# mos.net
KiCad netlist of a schematic drawn in Altium Designer
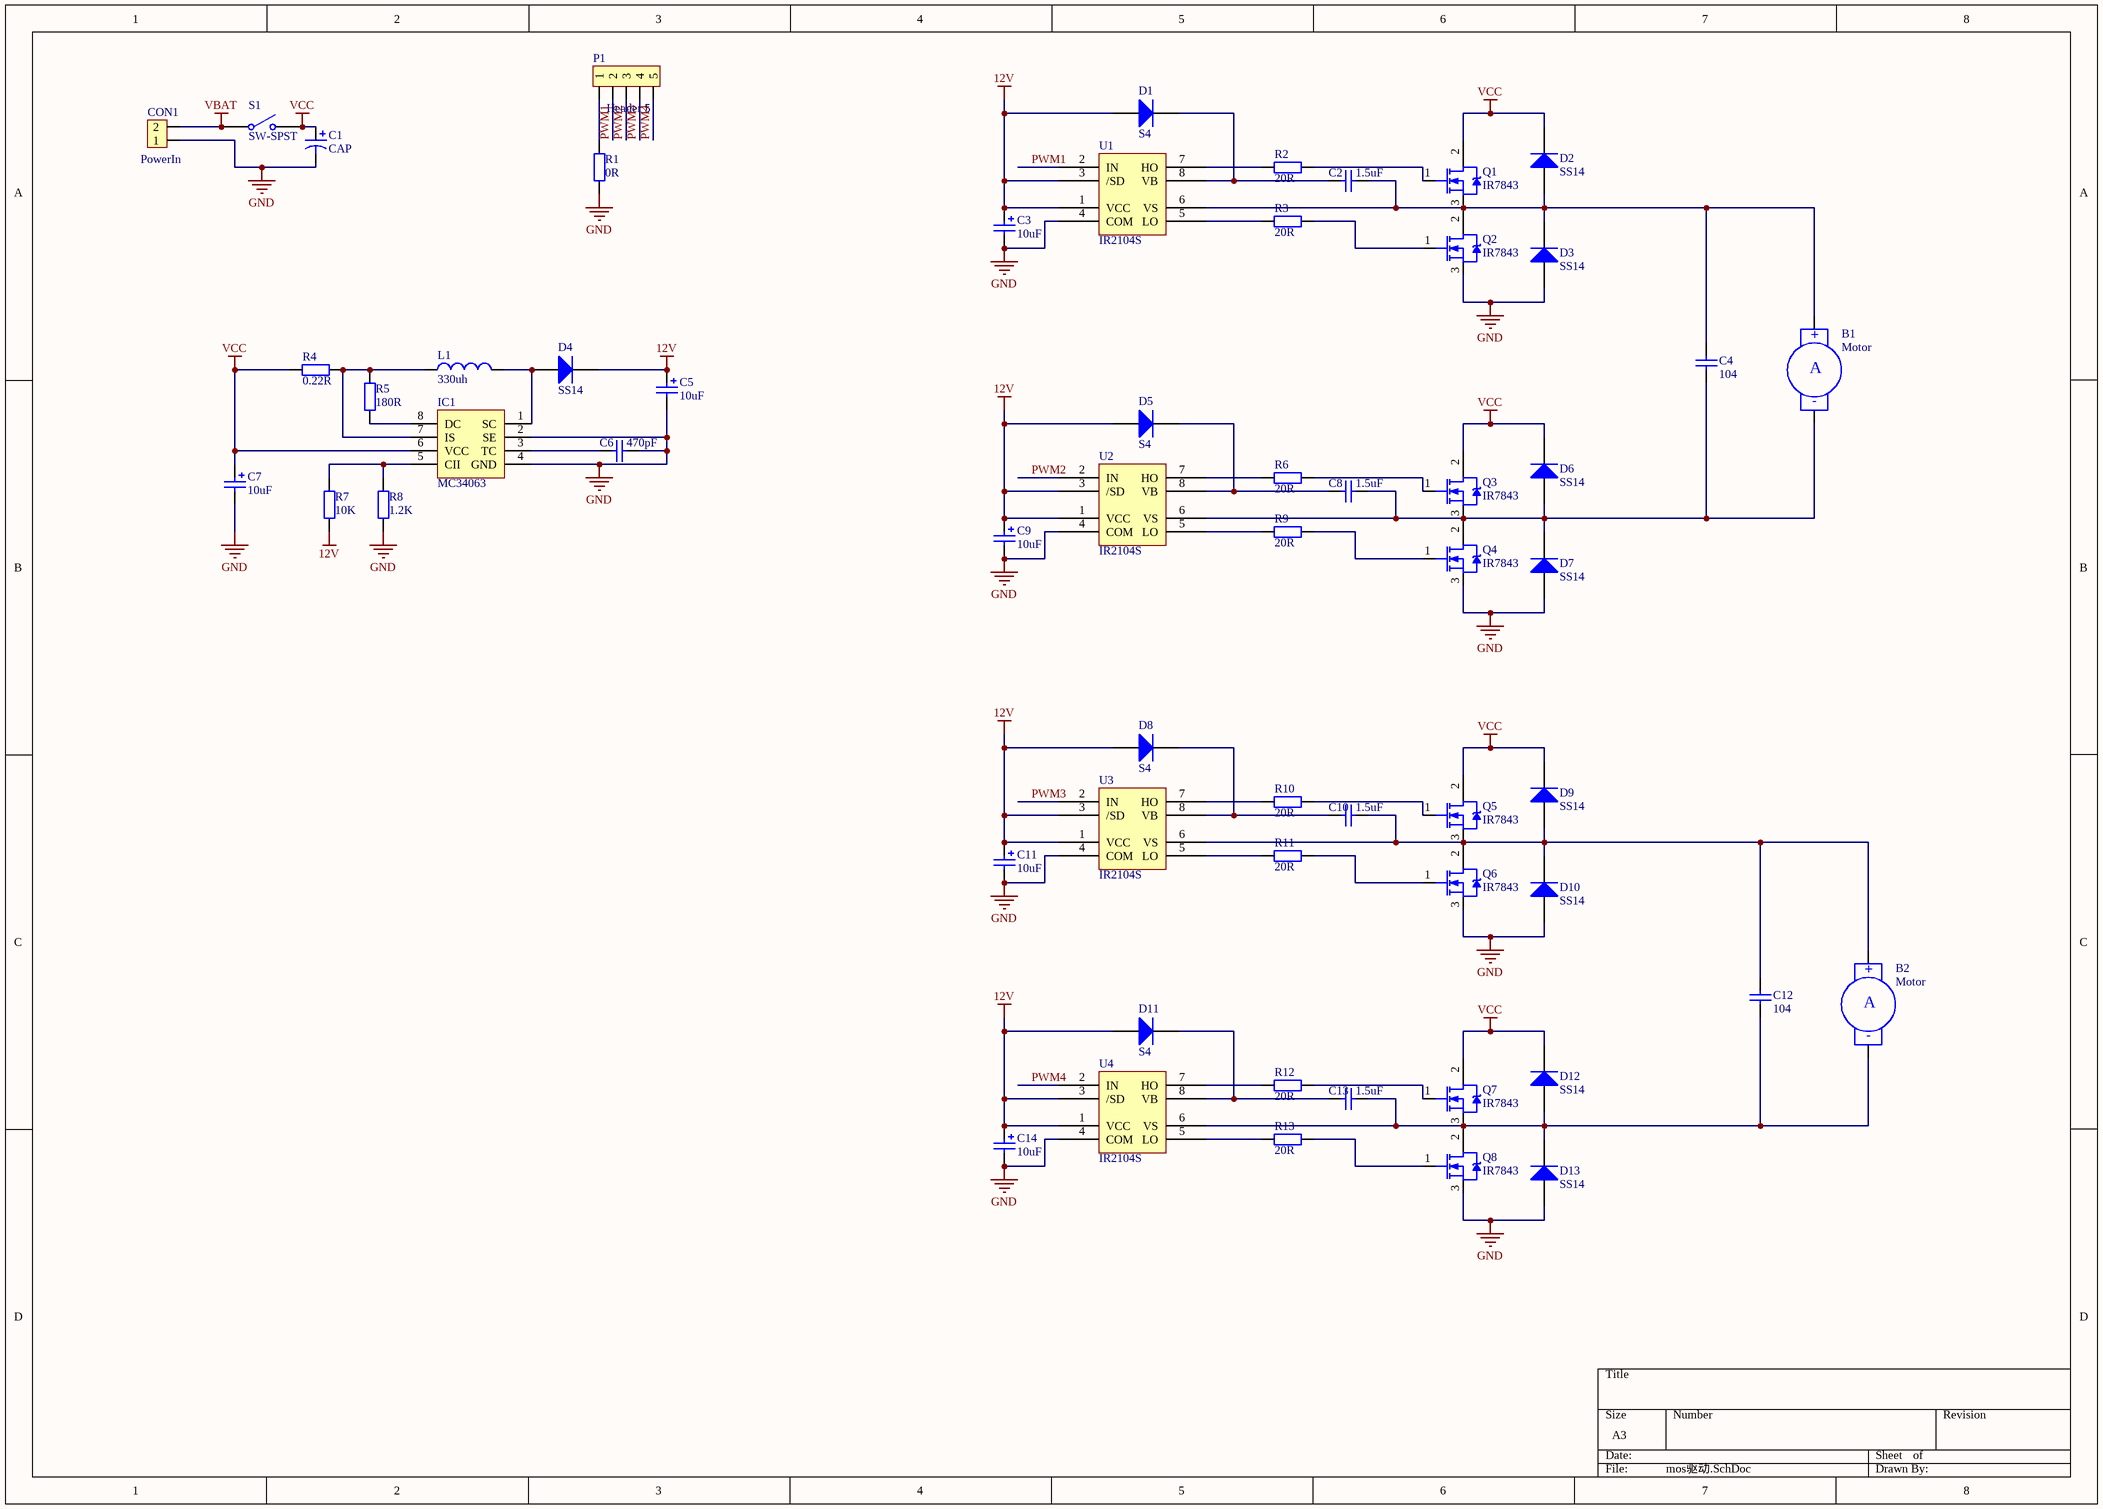
[diagram p0: mos驱动.SchDoc]

(export (version "E")
  (design (tool "Eeschema 10.0.6"))
  (components
    (comp (ref "B1")
      (value "Motor")
      (footprint "KF301-2P")
      (description "Servo Motor")
      (libsource (lib "landzo_mos") (part "Motor Servo"))
    )
    (comp (ref "B2")
      (value "Motor")
      (footprint "KF301-2P")
      (description "Servo Motor")
      (libsource (lib "landzo_mos") (part "Motor Servo"))
    )
    (comp (ref "C1") (value "CAP") (footprint "SMD-EC-F12.5") (libsource (lib "电赛") (part "CAP+")))
    (comp (ref "C2")
      (value "1.5uF")
      (footprint "C2012")
      (description "Capacitor")
      (fields (field (name "Comment") "Cap") (field (name "PUBLISHER") "Altium Limited"))
      (libsource (lib "Miscellaneous Devices") (part "Cap"))
    )
    (comp (ref "C3")
      (value "10uF")
      (footprint "C2012")
      (description "Polarized Capacitor (Radial)")
      (fields (field (name "Comment") "Cap Pol1") (field (name "PUBLISHER") "Altium Limited"))
      (libsource (lib "landzo_mos") (part "Cap Pol1"))
    )
    (comp (ref "C4")
      (value "104")
      (footprint "C2012")
      (description "Capacitor")
      (fields (field (name "Comment") "Cap") (field (name "PUBLISHER") "Altium Limited"))
      (libsource (lib "Miscellaneous Devices") (part "Cap"))
    )
    (comp (ref "C5")
      (value "10uF")
      (footprint "1206C")
      (description "Polarized Capacitor (Radial)")
      (fields (field (name "Comment") "Cap Pol1") (field (name "PUBLISHER") "Altium Limited"))
      (libsource (lib "landzo_mos") (part "Cap Pol1"))
    )
    (comp (ref "C6")
      (value "470pF")
      (footprint "C2012")
      (description "Capacitor")
      (fields (field (name "Comment") "Cap") (field (name "PUBLISHER") "Altium Limited"))
      (libsource (lib "Miscellaneous Devices") (part "Cap"))
    )
    (comp (ref "C7")
      (value "10uF")
      (footprint "1206C")
      (description "Polarized Capacitor (Radial)")
      (fields (field (name "Comment") "Cap Pol1") (field (name "PUBLISHER") "Altium Limited"))
      (libsource (lib "landzo_mos") (part "Cap Pol1"))
    )
    (comp (ref "C8")
      (value "1.5uF")
      (footprint "C2012")
      (description "Capacitor")
      (fields (field (name "Comment") "Cap") (field (name "PUBLISHER") "Altium Limited"))
      (libsource (lib "Miscellaneous Devices") (part "Cap"))
    )
    (comp (ref "C9")
      (value "10uF")
      (footprint "C2012")
      (description "Polarized Capacitor (Radial)")
      (fields (field (name "Comment") "Cap Pol1") (field (name "PUBLISHER") "Altium Limited"))
      (libsource (lib "landzo_mos") (part "Cap Pol1"))
    )
    (comp (ref "C10")
      (value "1.5uF")
      (footprint "C2012")
      (description "Capacitor")
      (fields (field (name "Comment") "Cap") (field (name "PUBLISHER") "Altium Limited"))
      (libsource (lib "Miscellaneous Devices") (part "Cap"))
    )
    (comp (ref "C11")
      (value "10uF")
      (footprint "C2012")
      (description "Polarized Capacitor (Radial)")
      (fields (field (name "Comment") "Cap Pol1") (field (name "PUBLISHER") "Altium Limited"))
      (libsource (lib "landzo_mos") (part "Cap Pol1"))
    )
    (comp (ref "C12")
      (value "104")
      (footprint "C2012")
      (description "Capacitor")
      (fields (field (name "Comment") "Cap") (field (name "PUBLISHER") "Altium Limited"))
      (libsource (lib "Miscellaneous Devices") (part "Cap"))
    )
    (comp (ref "C13")
      (value "1.5uF")
      (footprint "C2012")
      (description "Capacitor")
      (fields (field (name "Comment") "Cap") (field (name "PUBLISHER") "Altium Limited"))
      (libsource (lib "Miscellaneous Devices") (part "Cap"))
    )
    (comp (ref "C14")
      (value "10uF")
      (footprint "C2012")
      (description "Polarized Capacitor (Radial)")
      (fields (field (name "Comment") "Cap Pol1") (field (name "PUBLISHER") "Altium Limited"))
      (libsource (lib "landzo_mos") (part "Cap Pol1"))
    )
    (comp (ref "CON1")
      (value "PowerIn")
      (footprint "KF301-2P")
      (description "Header, 2-Pin")
      (libsource (lib "landzo_mos") (part "Header 2"))
    )
    (comp (ref "D1")
      (value "S4")
      (footprint "R2012")
      (description "1 Amp General Purpose Rectifier")
      (fields (field (name "PUBLISHER") "Altium Limited"))
      (libsource (lib "Miscellaneous Devices") (part "Diode 1N4007"))
    )
    (comp (ref "D2")
      (value "SS14")
      (footprint "hole-chip diode")
      (description "1 Amp General Purpose Rectifier")
      (fields (field (name "PUBLISHER") "Altium Limited"))
      (libsource (lib "Miscellaneous Devices") (part "Diode 1N4007"))
    )
    (comp (ref "D3")
      (value "SS14")
      (footprint "hole-chip diode")
      (description "1 Amp General Purpose Rectifier")
      (fields (field (name "PUBLISHER") "Altium Limited"))
      (libsource (lib "Miscellaneous Devices") (part "Diode 1N4007"))
    )
    (comp (ref "D4")
      (value "SS14")
      (footprint "hole-chip diode")
      (description "1 Amp General Purpose Rectifier")
      (fields (field (name "PUBLISHER") "Altium Limited"))
      (libsource (lib "Miscellaneous Devices") (part "Diode 1N4007"))
    )
    (comp (ref "D5")
      (value "S4")
      (footprint "R2012")
      (description "1 Amp General Purpose Rectifier")
      (fields (field (name "PUBLISHER") "Altium Limited"))
      (libsource (lib "Miscellaneous Devices") (part "Diode 1N4007"))
    )
    (comp (ref "D6")
      (value "SS14")
      (footprint "hole-chip diode")
      (description "1 Amp General Purpose Rectifier")
      (fields (field (name "PUBLISHER") "Altium Limited"))
      (libsource (lib "Miscellaneous Devices") (part "Diode 1N4007"))
    )
    (comp (ref "D7")
      (value "SS14")
      (footprint "hole-chip diode")
      (description "1 Amp General Purpose Rectifier")
      (fields (field (name "PUBLISHER") "Altium Limited"))
      (libsource (lib "Miscellaneous Devices") (part "Diode 1N4007"))
    )
    (comp (ref "D8")
      (value "S4")
      (footprint "R2012")
      (description "1 Amp General Purpose Rectifier")
      (fields (field (name "PUBLISHER") "Altium Limited"))
      (libsource (lib "Miscellaneous Devices") (part "Diode 1N4007"))
    )
    (comp (ref "D9")
      (value "SS14")
      (footprint "hole-chip diode")
      (description "1 Amp General Purpose Rectifier")
      (fields (field (name "PUBLISHER") "Altium Limited"))
      (libsource (lib "Miscellaneous Devices") (part "Diode 1N4007"))
    )
    (comp (ref "D10")
      (value "SS14")
      (footprint "hole-chip diode")
      (description "1 Amp General Purpose Rectifier")
      (fields (field (name "PUBLISHER") "Altium Limited"))
      (libsource (lib "Miscellaneous Devices") (part "Diode 1N4007"))
    )
    (comp (ref "D11")
      (value "S4")
      (footprint "R2012")
      (description "1 Amp General Purpose Rectifier")
      (fields (field (name "PUBLISHER") "Altium Limited"))
      (libsource (lib "Miscellaneous Devices") (part "Diode 1N4007"))
    )
    (comp (ref "D12")
      (value "SS14")
      (footprint "hole-chip diode")
      (description "1 Amp General Purpose Rectifier")
      (fields (field (name "PUBLISHER") "Altium Limited"))
      (libsource (lib "Miscellaneous Devices") (part "Diode 1N4007"))
    )
    (comp (ref "D13")
      (value "SS14")
      (footprint "hole-chip diode")
      (description "1 Amp General Purpose Rectifier")
      (fields (field (name "PUBLISHER") "Altium Limited"))
      (libsource (lib "Miscellaneous Devices") (part "Diode 1N4007"))
    )
    (comp (ref "IC1") (value "MC34063") (footprint "SO-8") (libsource (lib "Landzo") (part "MC34063")))
    (comp (ref "L1")
      (value "330uh")
      (footprint "SMD-EC-F8")
      (description "Inductor")
      (fields (field (name "PUBLISHER") "Altium Limited"))
      (libsource (lib "landzo_mos") (part "Inductor"))
    )
    (comp (ref "P1")
      (value "Header 5")
      (footprint "2.54XD_5")
      (description "Header, 5-Pin")
      (libsource (lib "landzo_mos") (part "Header 5"))
    )
    (comp (ref "Q1")
      (value "IR7843")
      (footprint "LR7843")
      (description "N-Channel Power MOSFET")
      (fields (field (name "PUBLISHER") "Altium Limited"))
      (libsource (lib "MOS motor driving module ") (part "NMOS-2"))
    )
    (comp (ref "Q2")
      (value "IR7843")
      (footprint "LR7843")
      (description "N-Channel Power MOSFET")
      (fields (field (name "PUBLISHER") "Altium Limited"))
      (libsource (lib "MOS motor driving module ") (part "NMOS-2"))
    )
    (comp (ref "Q3")
      (value "IR7843")
      (footprint "LR7843")
      (description "N-Channel Power MOSFET")
      (fields (field (name "PUBLISHER") "Altium Limited"))
      (libsource (lib "MOS motor driving module ") (part "NMOS-2"))
    )
    (comp (ref "Q4")
      (value "IR7843")
      (footprint "LR7843")
      (description "N-Channel Power MOSFET")
      (fields (field (name "PUBLISHER") "Altium Limited"))
      (libsource (lib "MOS motor driving module ") (part "NMOS-2"))
    )
    (comp (ref "Q5")
      (value "IR7843")
      (footprint "LR7843")
      (description "N-Channel Power MOSFET")
      (fields (field (name "PUBLISHER") "Altium Limited"))
      (libsource (lib "MOS motor driving module ") (part "NMOS-2"))
    )
    (comp (ref "Q6")
      (value "IR7843")
      (footprint "LR7843")
      (description "N-Channel Power MOSFET")
      (fields (field (name "PUBLISHER") "Altium Limited"))
      (libsource (lib "MOS motor driving module ") (part "NMOS-2"))
    )
    (comp (ref "Q7")
      (value "IR7843")
      (footprint "LR7843")
      (description "N-Channel Power MOSFET")
      (fields (field (name "PUBLISHER") "Altium Limited"))
      (libsource (lib "MOS motor driving module ") (part "NMOS-2"))
    )
    (comp (ref "Q8")
      (value "IR7843")
      (footprint "LR7843")
      (description "N-Channel Power MOSFET")
      (fields (field (name "PUBLISHER") "Altium Limited"))
      (libsource (lib "MOS motor driving module ") (part "NMOS-2"))
    )
    (comp (ref "R1")
      (value "0R")
      (footprint "1206(2)")
      (description "Resistor")
      (fields (field (name "Comment") "Res2") (field (name "PUBLISHER") "Altium Limited"))
      (libsource (lib "landzo_mos") (part "Res2"))
    )
    (comp (ref "R2")
      (value "20R")
      (footprint "R2012")
      (description "Resistor")
      (fields (field (name "Comment") "Res2") (field (name "PUBLISHER") "Altium Limited"))
      (libsource (lib "") (part "Res2_1"))
    )
    (comp (ref "R3")
      (value "20R")
      (footprint "R2012")
      (description "Resistor")
      (fields (field (name "Comment") "Res2") (field (name "PUBLISHER") "Altium Limited"))
      (libsource (lib "") (part "Res2_1"))
    )
    (comp (ref "R4")
      (value "0.22R")
      (footprint "R2012")
      (description "Resistor")
      (fields (field (name "Comment") "Res2") (field (name "PUBLISHER") "Altium Limited"))
      (libsource (lib "") (part "Res2_1"))
    )
    (comp (ref "R5")
      (value "180R")
      (footprint "R2012")
      (description "Resistor")
      (fields (field (name "Comment") "Res2") (field (name "PUBLISHER") "Altium Limited"))
      (libsource (lib "landzo_mos") (part "Res2"))
    )
    (comp (ref "R6")
      (value "20R")
      (footprint "R2012")
      (description "Resistor")
      (fields (field (name "Comment") "Res2") (field (name "PUBLISHER") "Altium Limited"))
      (libsource (lib "") (part "Res2_1"))
    )
    (comp (ref "R7")
      (value "10K")
      (footprint "R2012")
      (description "Resistor")
      (fields (field (name "Comment") "Res2") (field (name "PUBLISHER") "Altium Limited"))
      (libsource (lib "landzo_mos") (part "Res2"))
    )
    (comp (ref "R8")
      (value "1.2K")
      (footprint "R2012")
      (description "Resistor")
      (fields (field (name "Comment") "Res2") (field (name "PUBLISHER") "Altium Limited"))
      (libsource (lib "landzo_mos") (part "Res2"))
    )
    (comp (ref "R9")
      (value "20R")
      (footprint "R2012")
      (description "Resistor")
      (fields (field (name "Comment") "Res2") (field (name "PUBLISHER") "Altium Limited"))
      (libsource (lib "") (part "Res2_1"))
    )
    (comp (ref "R10")
      (value "20R")
      (footprint "R2012")
      (description "Resistor")
      (fields (field (name "Comment") "Res2") (field (name "PUBLISHER") "Altium Limited"))
      (libsource (lib "") (part "Res2_1"))
    )
    (comp (ref "R11")
      (value "20R")
      (footprint "R2012")
      (description "Resistor")
      (fields (field (name "Comment") "Res2") (field (name "PUBLISHER") "Altium Limited"))
      (libsource (lib "") (part "Res2_1"))
    )
    (comp (ref "R12")
      (value "20R")
      (footprint "R2012")
      (description "Resistor")
      (fields (field (name "Comment") "Res2") (field (name "PUBLISHER") "Altium Limited"))
      (libsource (lib "") (part "Res2_1"))
    )
    (comp (ref "R13")
      (value "20R")
      (footprint "R2012")
      (description "Resistor")
      (fields (field (name "Comment") "Res2") (field (name "PUBLISHER") "Altium Limited"))
      (libsource (lib "") (part "Res2_1"))
    )
    (comp (ref "S1")
      (value "SW-SPST")
      (footprint "SW-125V6A(-)")
      (description "Single-Pole, Single-Throw Switch")
      (fields (field (name "PUBLISHER") "Altium Limited"))
      (libsource (lib "Miscellaneous Devices") (part "SW-SPST"))
    )
    (comp (ref "U1")
      (value "IR2104S")
      (footprint "IR2104")
      (libsource (lib "MOS motor driving module ") (part "Component_1_1"))
    )
    (comp (ref "U2")
      (value "IR2104S")
      (footprint "IR2104")
      (libsource (lib "MOS motor driving module ") (part "Component_1_1"))
    )
    (comp (ref "U3")
      (value "IR2104S")
      (footprint "IR2104")
      (libsource (lib "MOS motor driving module ") (part "Component_1_1"))
    )
    (comp (ref "U4")
      (value "IR2104S")
      (footprint "IR2104")
      (libsource (lib "MOS motor driving module ") (part "Component_1_1"))
    )
  )
  (nets
    (net (code "1") (name "/PWM1") (class "Default")
      (node (ref "P1") (pin "2") (pinfunction "2_2") (pintype "passive"))
      (node (ref "U1") (pin "2") (pinfunction "IN_2") (pintype "passive"))
    )
    (net (code "2") (name "/PWM2") (class "Default")
      (node (ref "P1") (pin "3") (pinfunction "3_3") (pintype "passive"))
      (node (ref "U2") (pin "2") (pinfunction "IN_2") (pintype "passive"))
    )
    (net (code "3") (name "/PWM3") (class "Default")
      (node (ref "P1") (pin "4") (pinfunction "4_4") (pintype "passive"))
      (node (ref "U3") (pin "2") (pinfunction "IN_2") (pintype "passive"))
    )
    (net (code "4") (name "/PWM4") (class "Default")
      (node (ref "P1") (pin "5") (pinfunction "5_5") (pintype "passive"))
      (node (ref "U4") (pin "2") (pinfunction "IN_2") (pintype "passive"))
    )
    (net (code "5") (name "12V") (class "Default")
      (node (ref "C11") (pin "1") (pinfunction "1_1") (pintype "passive"))
      (node (ref "C14") (pin "1") (pinfunction "1_1") (pintype "passive"))
      (node (ref "C3") (pin "1") (pinfunction "1_1") (pintype "passive"))
      (node (ref "C5") (pin "1") (pinfunction "1_1") (pintype "passive"))
      (node (ref "C9") (pin "1") (pinfunction "1_1") (pintype "passive"))
      (node (ref "D1") (pin "1") (pinfunction "A_1") (pintype "passive"))
      (node (ref "D11") (pin "1") (pinfunction "A_1") (pintype "passive"))
      (node (ref "D4") (pin "2") (pinfunction "K_2") (pintype "passive"))
      (node (ref "D5") (pin "1") (pinfunction "A_1") (pintype "passive"))
      (node (ref "D8") (pin "1") (pinfunction "A_1") (pintype "passive"))
      (node (ref "R7") (pin "1") (pinfunction "1_1") (pintype "passive"))
      (node (ref "U1") (pin "1") (pinfunction "VCC_1") (pintype "passive"))
      (node (ref "U1") (pin "3") (pinfunction "/SD_3") (pintype "passive"))
      (node (ref "U2") (pin "1") (pinfunction "VCC_1") (pintype "passive"))
      (node (ref "U2") (pin "3") (pinfunction "/SD_3") (pintype "passive"))
      (node (ref "U3") (pin "1") (pinfunction "VCC_1") (pintype "passive"))
      (node (ref "U3") (pin "3") (pinfunction "/SD_3") (pintype "passive"))
      (node (ref "U4") (pin "1") (pinfunction "VCC_1") (pintype "passive"))
      (node (ref "U4") (pin "3") (pinfunction "/SD_3") (pintype "passive"))
    )
    (net (code "6") (name "GND") (class "Default")
      (node (ref "C1") (pin "2") (pinfunction "2_2") (pintype "passive"))
      (node (ref "C11") (pin "2") (pinfunction "2_2") (pintype "passive"))
      (node (ref "C14") (pin "2") (pinfunction "2_2") (pintype "passive"))
      (node (ref "C3") (pin "2") (pinfunction "2_2") (pintype "passive"))
      (node (ref "C5") (pin "2") (pinfunction "2_2") (pintype "passive"))
      (node (ref "C6") (pin "1") (pinfunction "1_1") (pintype "passive"))
      (node (ref "C7") (pin "2") (pinfunction "2_2") (pintype "passive"))
      (node (ref "C9") (pin "2") (pinfunction "2_2") (pintype "passive"))
      (node (ref "CON1") (pin "1") (pinfunction "1_1") (pintype "passive"))
      (node (ref "D10") (pin "1") (pinfunction "A_1") (pintype "passive"))
      (node (ref "D13") (pin "1") (pinfunction "A_1") (pintype "passive"))
      (node (ref "D3") (pin "1") (pinfunction "A_1") (pintype "passive"))
      (node (ref "D7") (pin "1") (pinfunction "A_1") (pintype "passive"))
      (node (ref "IC1") (pin "2") (pinfunction "SE_2") (pintype "passive"))
      (node (ref "IC1") (pin "4") (pinfunction "GND_4") (pintype "passive"))
      (node (ref "Q2") (pin "3") (pinfunction "S_3") (pintype "passive"))
      (node (ref "Q4") (pin "3") (pinfunction "S_3") (pintype "passive"))
      (node (ref "Q6") (pin "3") (pinfunction "S_3") (pintype "passive"))
      (node (ref "Q8") (pin "3") (pinfunction "S_3") (pintype "passive"))
      (node (ref "R1") (pin "1") (pinfunction "1_1") (pintype "passive"))
      (node (ref "R8") (pin "1") (pinfunction "1_1") (pintype "passive"))
      (node (ref "U1") (pin "4") (pinfunction "COM_4") (pintype "passive"))
      (node (ref "U2") (pin "4") (pinfunction "COM_4") (pintype "passive"))
      (node (ref "U3") (pin "4") (pinfunction "COM_4") (pintype "passive"))
      (node (ref "U4") (pin "4") (pinfunction "COM_4") (pintype "passive"))
    )
    (net (code "7") (name "Net-(B1-+)") (class "Default")
      (node (ref "B1") (pin "1") (pinfunction "+_1") (pintype "passive"))
      (node (ref "C2") (pin "1") (pinfunction "1_1") (pintype "passive"))
      (node (ref "C4") (pin "1") (pinfunction "1_1") (pintype "passive"))
      (node (ref "D2") (pin "1") (pinfunction "A_1") (pintype "passive"))
      (node (ref "D3") (pin "2") (pinfunction "K_2") (pintype "passive"))
      (node (ref "Q1") (pin "3") (pinfunction "S_3") (pintype "passive"))
      (node (ref "Q2") (pin "2") (pinfunction "D_2") (pintype "passive"))
      (node (ref "U1") (pin "6") (pinfunction "VS_6") (pintype "passive"))
    )
    (net (code "8") (name "Net-(B1--)") (class "Default")
      (node (ref "B1") (pin "2") (pinfunction "-_2") (pintype "passive"))
      (node (ref "C4") (pin "2") (pinfunction "2_2") (pintype "passive"))
      (node (ref "C8") (pin "1") (pinfunction "1_1") (pintype "passive"))
      (node (ref "D6") (pin "1") (pinfunction "A_1") (pintype "passive"))
      (node (ref "D7") (pin "2") (pinfunction "K_2") (pintype "passive"))
      (node (ref "Q3") (pin "3") (pinfunction "S_3") (pintype "passive"))
      (node (ref "Q4") (pin "2") (pinfunction "D_2") (pintype "passive"))
      (node (ref "U2") (pin "6") (pinfunction "VS_6") (pintype "passive"))
    )
    (net (code "9") (name "Net-(B2-+)") (class "Default")
      (node (ref "B2") (pin "1") (pinfunction "+_1") (pintype "passive"))
      (node (ref "C10") (pin "1") (pinfunction "1_1") (pintype "passive"))
      (node (ref "C12") (pin "1") (pinfunction "1_1") (pintype "passive"))
      (node (ref "D10") (pin "2") (pinfunction "K_2") (pintype "passive"))
      (node (ref "D9") (pin "1") (pinfunction "A_1") (pintype "passive"))
      (node (ref "Q5") (pin "3") (pinfunction "S_3") (pintype "passive"))
      (node (ref "Q6") (pin "2") (pinfunction "D_2") (pintype "passive"))
      (node (ref "U3") (pin "6") (pinfunction "VS_6") (pintype "passive"))
    )
    (net (code "10") (name "Net-(B2--)") (class "Default")
      (node (ref "B2") (pin "2") (pinfunction "-_2") (pintype "passive"))
      (node (ref "C12") (pin "2") (pinfunction "2_2") (pintype "passive"))
      (node (ref "C13") (pin "1") (pinfunction "1_1") (pintype "passive"))
      (node (ref "D12") (pin "1") (pinfunction "A_1") (pintype "passive"))
      (node (ref "D13") (pin "2") (pinfunction "K_2") (pintype "passive"))
      (node (ref "Q7") (pin "3") (pinfunction "S_3") (pintype "passive"))
      (node (ref "Q8") (pin "2") (pinfunction "D_2") (pintype "passive"))
      (node (ref "U4") (pin "6") (pinfunction "VS_6") (pintype "passive"))
    )
    (net (code "11") (name "Net-(D1-K)") (class "Default")
      (node (ref "C2") (pin "2") (pinfunction "2_2") (pintype "passive"))
      (node (ref "D1") (pin "2") (pinfunction "K_2") (pintype "passive"))
      (node (ref "U1") (pin "8") (pinfunction "VB_8") (pintype "passive"))
    )
    (net (code "12") (name "Net-(D4-A)") (class "Default")
      (node (ref "D4") (pin "1") (pinfunction "A_1") (pintype "passive"))
      (node (ref "IC1") (pin "1") (pinfunction "SC_1") (pintype "passive"))
      (node (ref "L1") (pin "2") (pinfunction "2_2") (pintype "passive"))
    )
    (net (code "13") (name "Net-(D5-K)") (class "Default")
      (node (ref "C8") (pin "2") (pinfunction "2_2") (pintype "passive"))
      (node (ref "D5") (pin "2") (pinfunction "K_2") (pintype "passive"))
      (node (ref "U2") (pin "8") (pinfunction "VB_8") (pintype "passive"))
    )
    (net (code "14") (name "Net-(D8-K)") (class "Default")
      (node (ref "C10") (pin "2") (pinfunction "2_2") (pintype "passive"))
      (node (ref "D8") (pin "2") (pinfunction "K_2") (pintype "passive"))
      (node (ref "U3") (pin "8") (pinfunction "VB_8") (pintype "passive"))
    )
    (net (code "15") (name "Net-(D11-K)") (class "Default")
      (node (ref "C13") (pin "2") (pinfunction "2_2") (pintype "passive"))
      (node (ref "D11") (pin "2") (pinfunction "K_2") (pintype "passive"))
      (node (ref "U4") (pin "8") (pinfunction "VB_8") (pintype "passive"))
    )
    (net (code "16") (name "Net-(IC1-CII)") (class "Default")
      (node (ref "IC1") (pin "5") (pinfunction "CII_5") (pintype "passive"))
      (node (ref "R7") (pin "2") (pinfunction "2_2") (pintype "passive"))
      (node (ref "R8") (pin "2") (pinfunction "2_2") (pintype "passive"))
    )
    (net (code "17") (name "Net-(IC1-DC)") (class "Default")
      (node (ref "IC1") (pin "8") (pinfunction "DC_8") (pintype "passive"))
      (node (ref "R5") (pin "1") (pinfunction "1_1") (pintype "passive"))
    )
    (net (code "18") (name "Net-(IC1-IS)") (class "Default")
      (node (ref "IC1") (pin "7") (pinfunction "IS_7") (pintype "passive"))
      (node (ref "L1") (pin "1") (pinfunction "1_1") (pintype "passive"))
      (node (ref "R4") (pin "2") (pinfunction "2_2") (pintype "passive"))
      (node (ref "R5") (pin "2") (pinfunction "2_2") (pintype "passive"))
    )
    (net (code "19") (name "Net-(IC1-TC)") (class "Default")
      (node (ref "C6") (pin "2") (pinfunction "2_2") (pintype "passive"))
      (node (ref "IC1") (pin "3") (pinfunction "TC_3") (pintype "passive"))
    )
    (net (code "20") (name "Net-(P1-Pad1)") (class "Default")
      (node (ref "P1") (pin "1") (pinfunction "1_1") (pintype "passive"))
      (node (ref "R1") (pin "2") (pinfunction "2_2") (pintype "passive"))
    )
    (net (code "21") (name "Net-(Q1-G)") (class "Default")
      (node (ref "Q1") (pin "1") (pinfunction "G_1") (pintype "passive"))
      (node (ref "R2") (pin "2") (pinfunction "2_2") (pintype "passive"))
    )
    (net (code "22") (name "Net-(Q2-G)") (class "Default")
      (node (ref "Q2") (pin "1") (pinfunction "G_1") (pintype "passive"))
      (node (ref "R3") (pin "2") (pinfunction "2_2") (pintype "passive"))
    )
    (net (code "23") (name "Net-(Q3-G)") (class "Default")
      (node (ref "Q3") (pin "1") (pinfunction "G_1") (pintype "passive"))
      (node (ref "R6") (pin "2") (pinfunction "2_2") (pintype "passive"))
    )
    (net (code "24") (name "Net-(Q4-G)") (class "Default")
      (node (ref "Q4") (pin "1") (pinfunction "G_1") (pintype "passive"))
      (node (ref "R9") (pin "2") (pinfunction "2_2") (pintype "passive"))
    )
    (net (code "25") (name "Net-(Q5-G)") (class "Default")
      (node (ref "Q5") (pin "1") (pinfunction "G_1") (pintype "passive"))
      (node (ref "R10") (pin "2") (pinfunction "2_2") (pintype "passive"))
    )
    (net (code "26") (name "Net-(Q6-G)") (class "Default")
      (node (ref "Q6") (pin "1") (pinfunction "G_1") (pintype "passive"))
      (node (ref "R11") (pin "2") (pinfunction "2_2") (pintype "passive"))
    )
    (net (code "27") (name "Net-(Q7-G)") (class "Default")
      (node (ref "Q7") (pin "1") (pinfunction "G_1") (pintype "passive"))
      (node (ref "R12") (pin "2") (pinfunction "2_2") (pintype "passive"))
    )
    (net (code "28") (name "Net-(Q8-G)") (class "Default")
      (node (ref "Q8") (pin "1") (pinfunction "G_1") (pintype "passive"))
      (node (ref "R13") (pin "2") (pinfunction "2_2") (pintype "passive"))
    )
    (net (code "29") (name "Net-(U1-HO)") (class "Default")
      (node (ref "R2") (pin "1") (pinfunction "1_1") (pintype "passive"))
      (node (ref "U1") (pin "7") (pinfunction "HO_7") (pintype "passive"))
    )
    (net (code "30") (name "Net-(U1-LO)") (class "Default")
      (node (ref "R3") (pin "1") (pinfunction "1_1") (pintype "passive"))
      (node (ref "U1") (pin "5") (pinfunction "LO_5") (pintype "passive"))
    )
    (net (code "31") (name "Net-(U2-HO)") (class "Default")
      (node (ref "R6") (pin "1") (pinfunction "1_1") (pintype "passive"))
      (node (ref "U2") (pin "7") (pinfunction "HO_7") (pintype "passive"))
    )
    (net (code "32") (name "Net-(U2-LO)") (class "Default")
      (node (ref "R9") (pin "1") (pinfunction "1_1") (pintype "passive"))
      (node (ref "U2") (pin "5") (pinfunction "LO_5") (pintype "passive"))
    )
    (net (code "33") (name "Net-(U3-HO)") (class "Default")
      (node (ref "R10") (pin "1") (pinfunction "1_1") (pintype "passive"))
      (node (ref "U3") (pin "7") (pinfunction "HO_7") (pintype "passive"))
    )
    (net (code "34") (name "Net-(U3-LO)") (class "Default")
      (node (ref "R11") (pin "1") (pinfunction "1_1") (pintype "passive"))
      (node (ref "U3") (pin "5") (pinfunction "LO_5") (pintype "passive"))
    )
    (net (code "35") (name "Net-(U4-HO)") (class "Default")
      (node (ref "R12") (pin "1") (pinfunction "1_1") (pintype "passive"))
      (node (ref "U4") (pin "7") (pinfunction "HO_7") (pintype "passive"))
    )
    (net (code "36") (name "Net-(U4-LO)") (class "Default")
      (node (ref "R13") (pin "1") (pinfunction "1_1") (pintype "passive"))
      (node (ref "U4") (pin "5") (pinfunction "LO_5") (pintype "passive"))
    )
    (net (code "37") (name "VBAT") (class "Default")
      (node (ref "CON1") (pin "2") (pinfunction "2_2") (pintype "passive"))
      (node (ref "S1") (pin "1") (pinfunction "COMMON_1") (pintype "passive"))
    )
    (net (code "38") (name "VCC") (class "Default")
      (node (ref "C1") (pin "1") (pinfunction "1_1") (pintype "passive"))
      (node (ref "C7") (pin "1") (pinfunction "1_1") (pintype "passive"))
      (node (ref "D12") (pin "2") (pinfunction "K_2") (pintype "passive"))
      (node (ref "D2") (pin "2") (pinfunction "K_2") (pintype "passive"))
      (node (ref "D6") (pin "2") (pinfunction "K_2") (pintype "passive"))
      (node (ref "D9") (pin "2") (pinfunction "K_2") (pintype "passive"))
      (node (ref "IC1") (pin "6") (pinfunction "VCC_6") (pintype "passive"))
      (node (ref "Q1") (pin "2") (pinfunction "D_2") (pintype "passive"))
      (node (ref "Q3") (pin "2") (pinfunction "D_2") (pintype "passive"))
      (node (ref "Q5") (pin "2") (pinfunction "D_2") (pintype "passive"))
      (node (ref "Q7") (pin "2") (pinfunction "D_2") (pintype "passive"))
      (node (ref "R4") (pin "1") (pinfunction "1_1") (pintype "passive"))
      (node (ref "S1") (pin "2") (pinfunction "NO_2") (pintype "passive"))
    )
  )
)
